# 4093_drone_synth.net
KiCad netlist of a schematic drawn in EAGLE
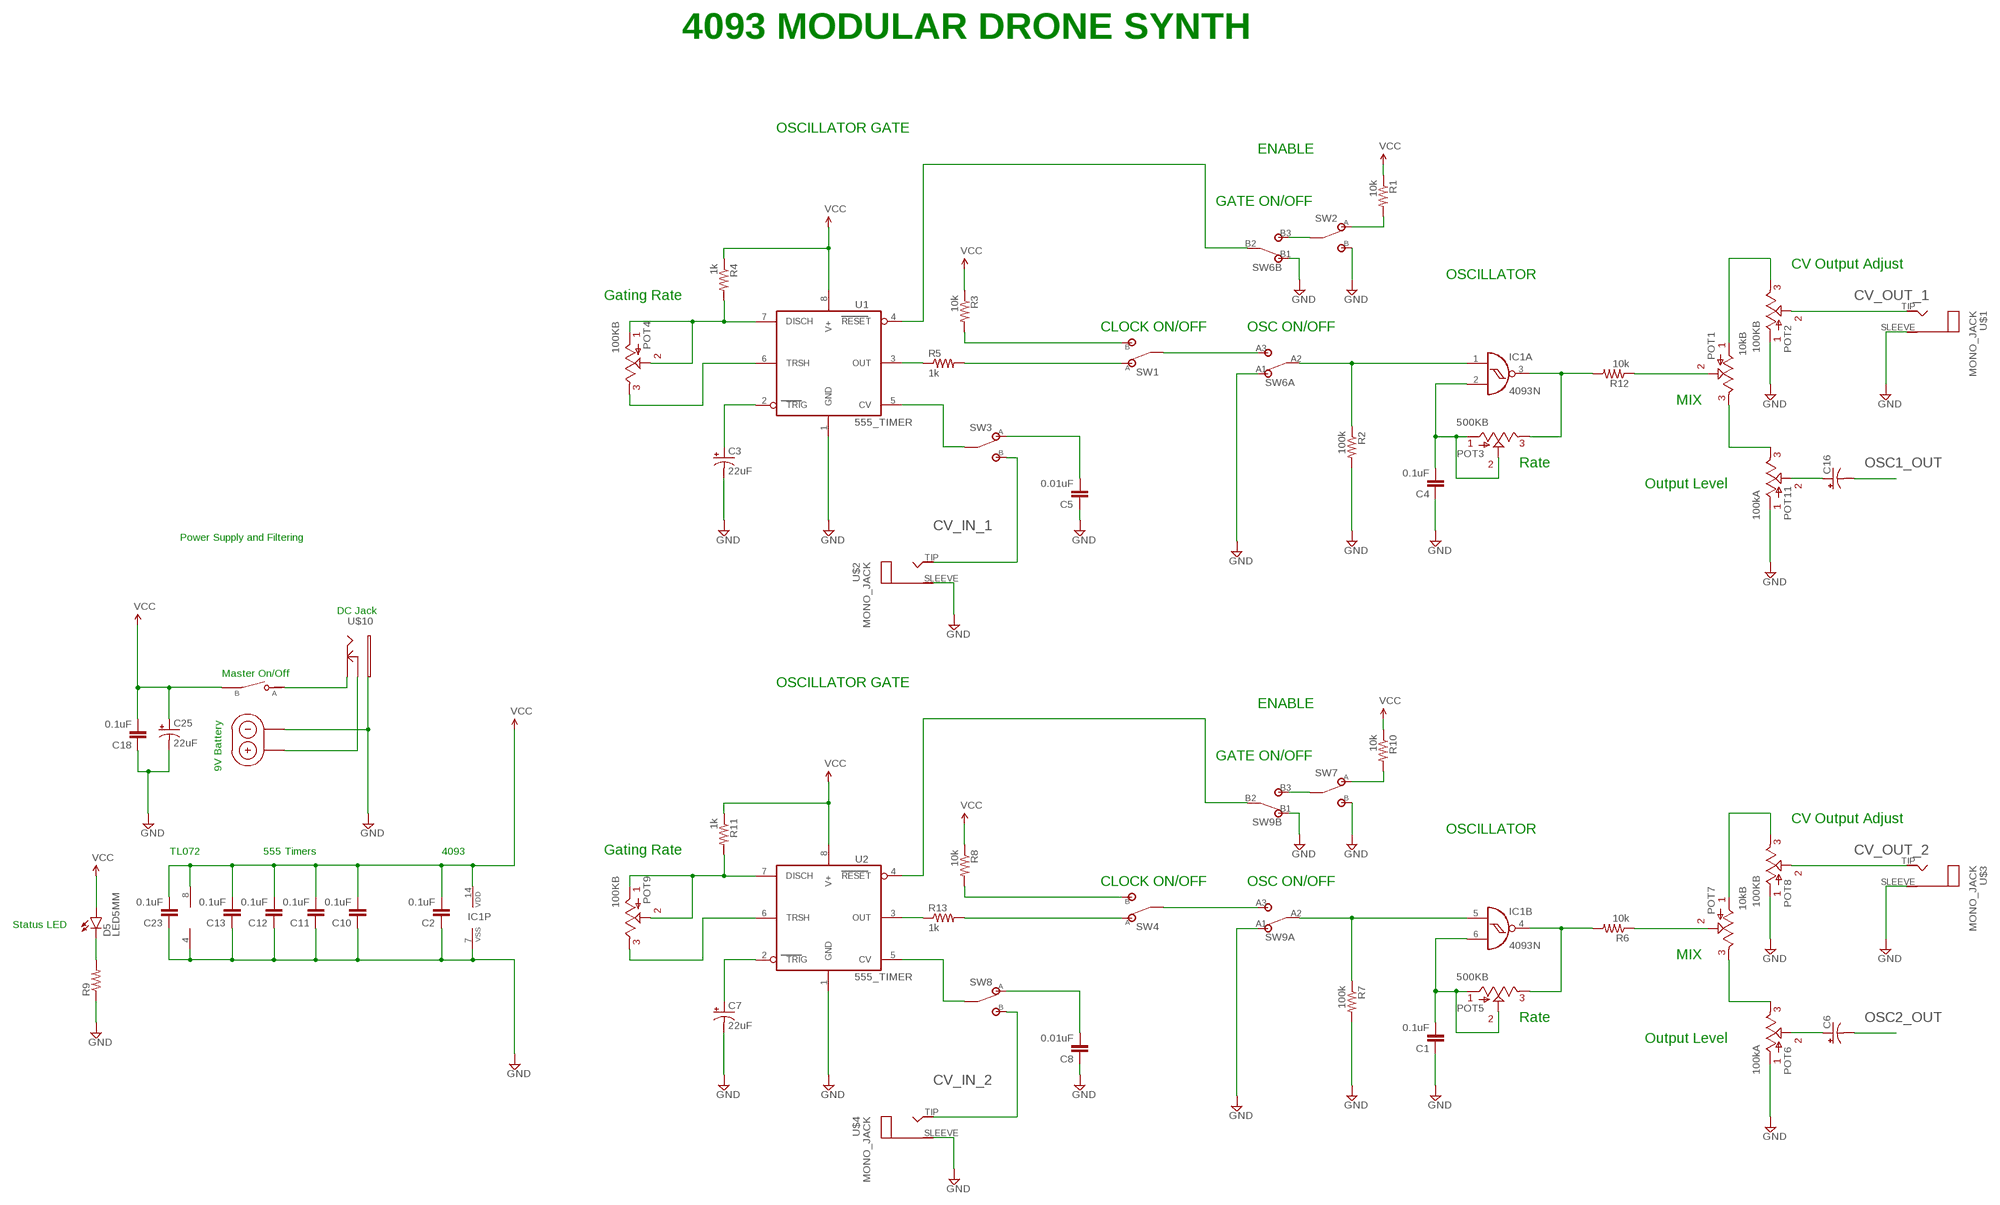
[diagram p0: schematic, sheet 1, part 1 of 3]
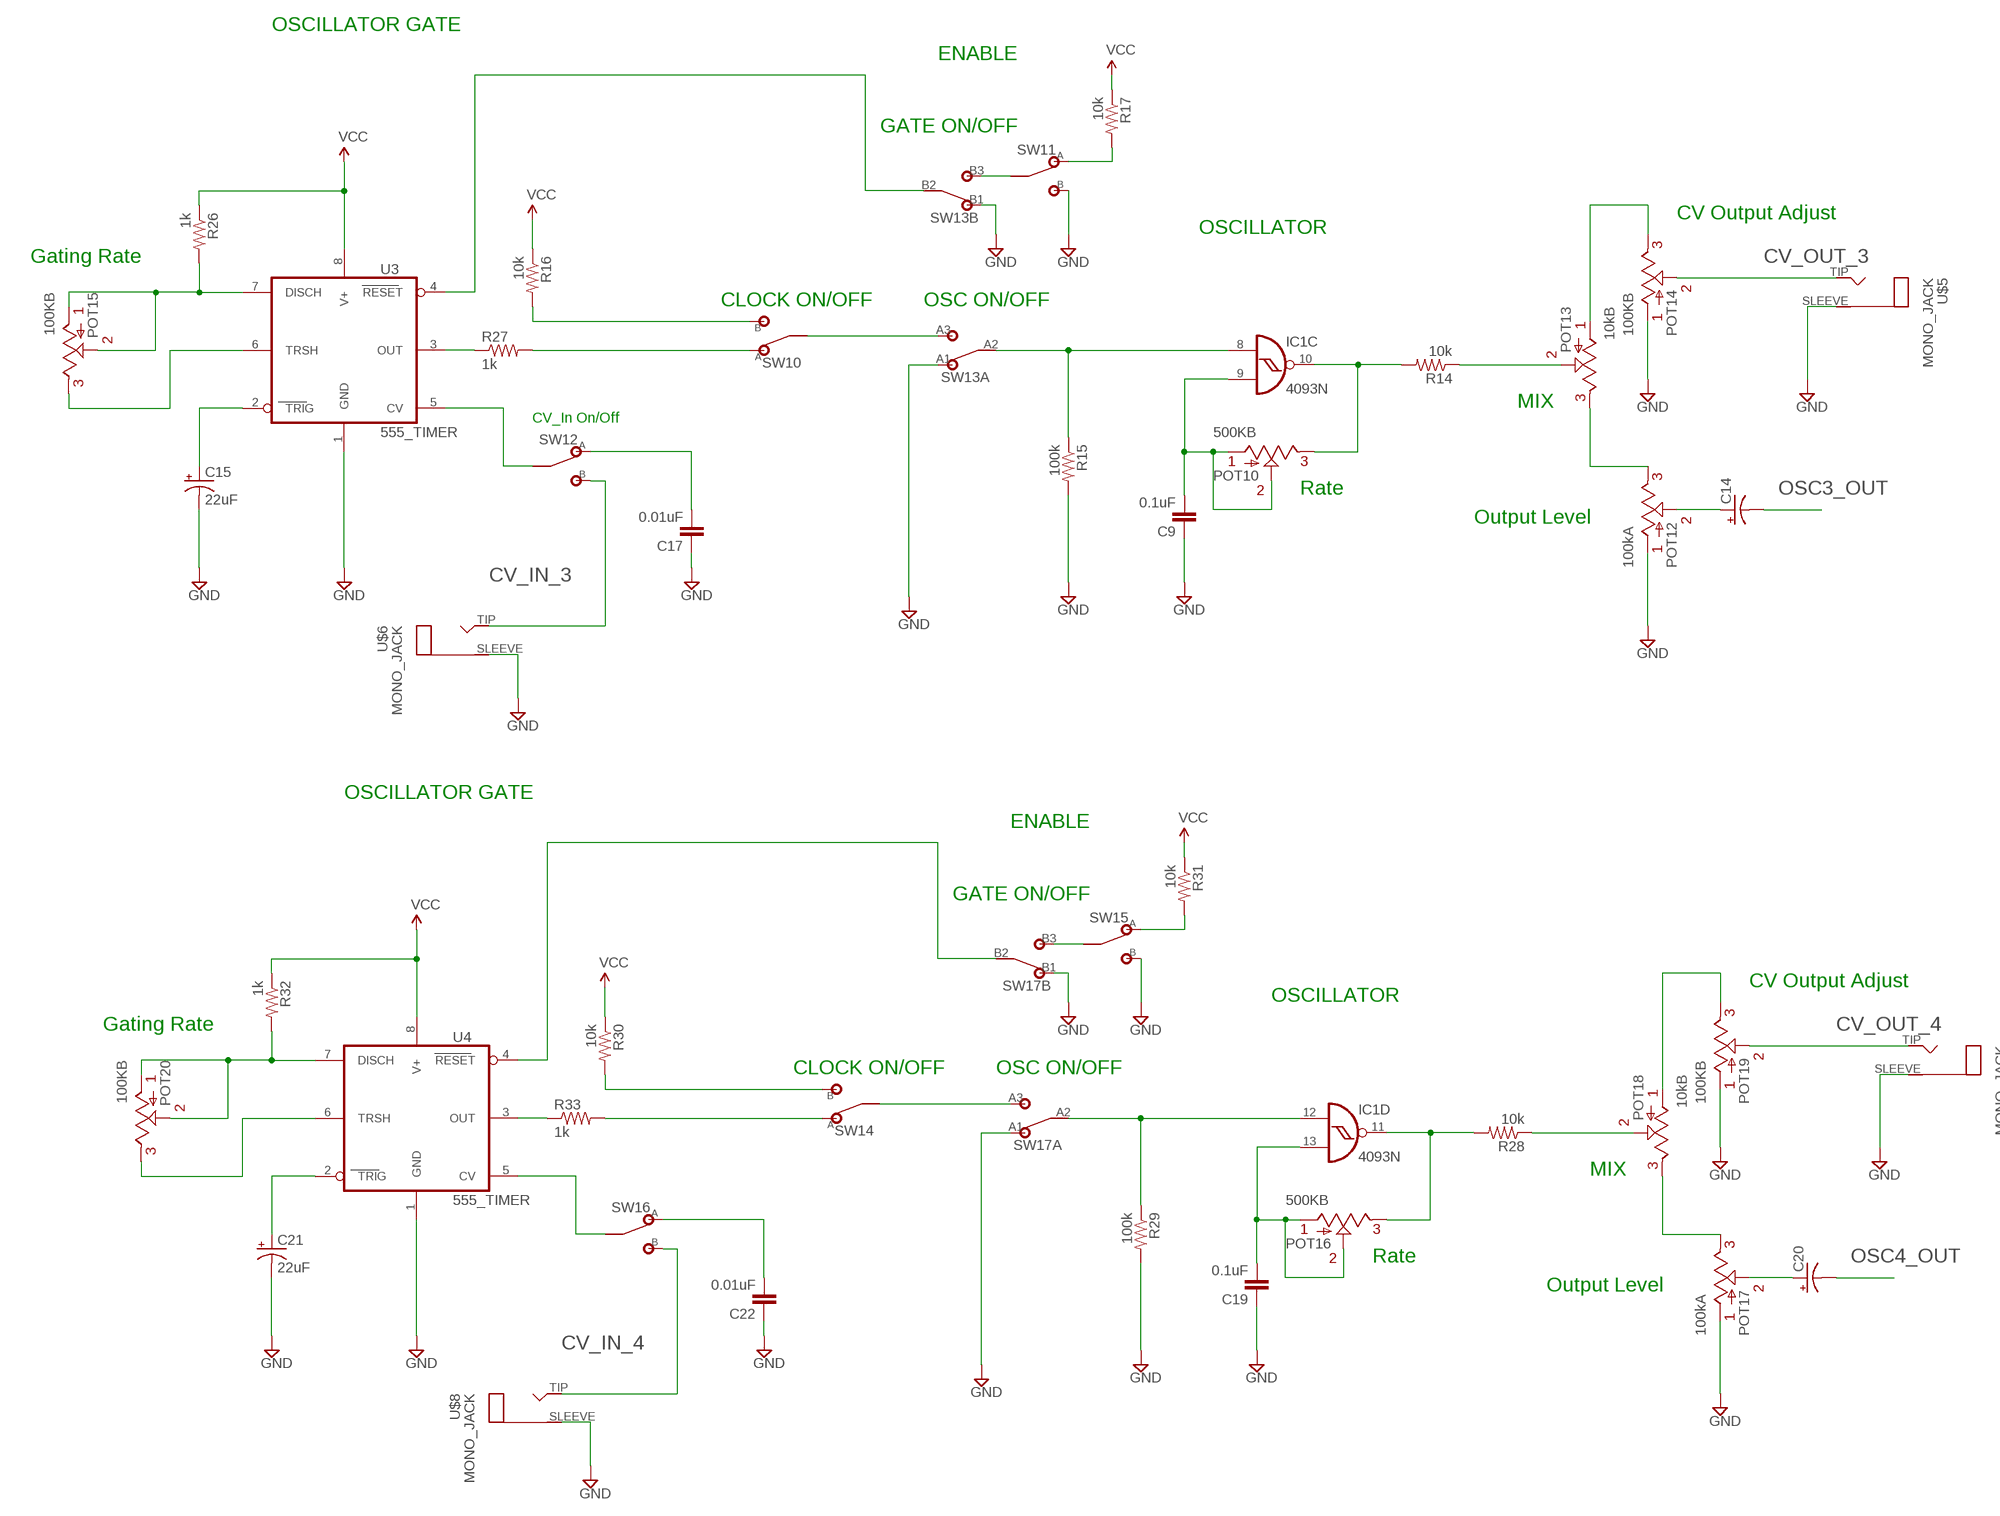
[diagram p1: schematic, sheet 1, part 2 of 3]
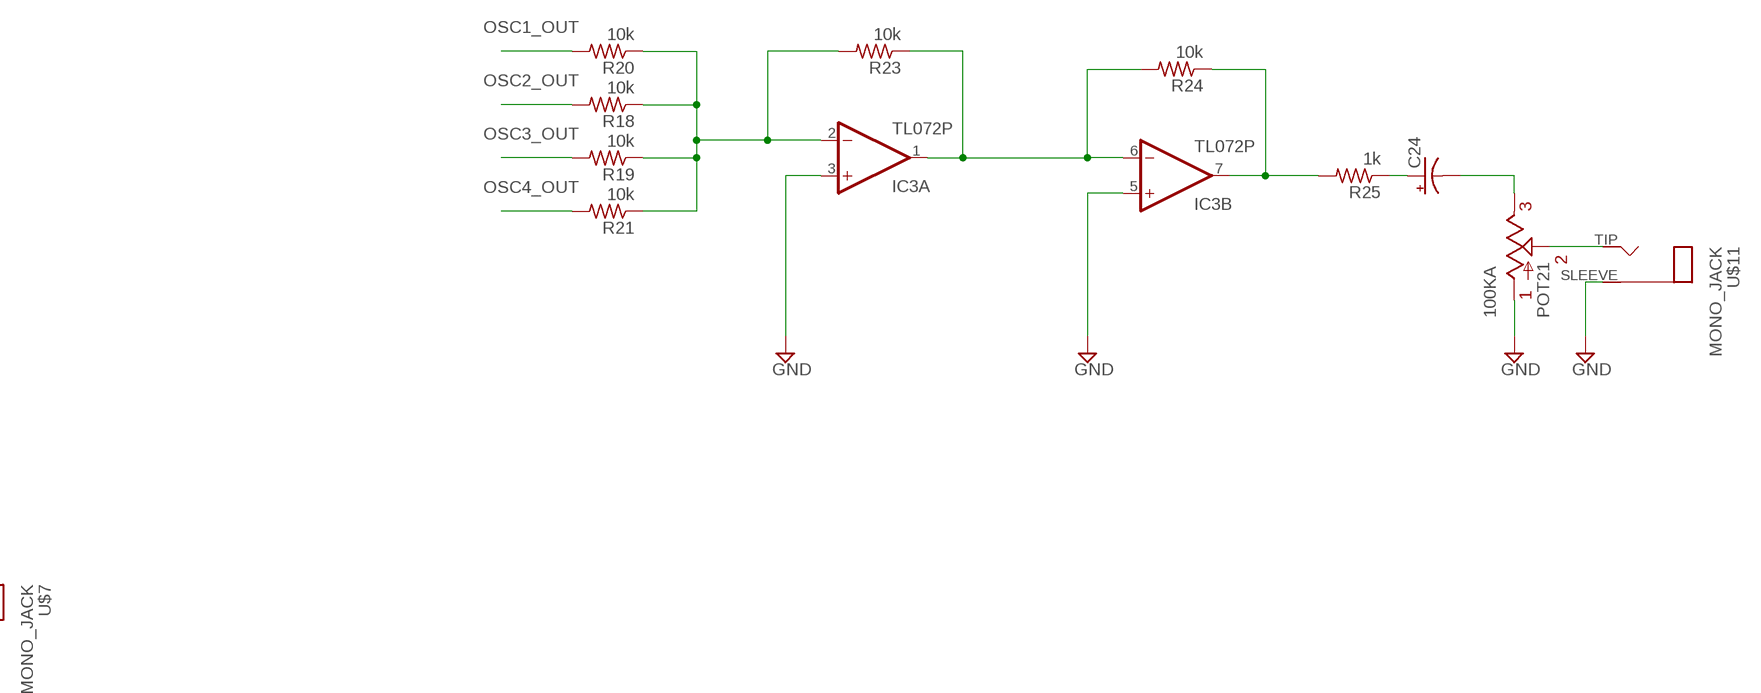
[diagram p2: schematic, sheet 1, part 3 of 3]

(export (version "E")
  (design (tool "Eeschema 10.0.6"))
  (components
    (comp (ref "C1")
      (value "0.1uF")
      (footprint "eagle-import:CERAMIC_CAP")
      (libsource (lib "eagle-import") (part "CERAMIC_CAPACITOR"))
    )
    (comp (ref "C2")
      (value "0.1uF")
      (footprint "eagle-import:CERAMIC_CAP")
      (libsource (lib "eagle-import") (part "CERAMIC_CAPACITOR"))
    )
    (comp (ref "C3")
      (value "22uF")
      (footprint "eagle-import:E5-10,5")
      (libsource (lib "eagle-import") (part "CPOL-USE5-10.5"))
    )
    (comp (ref "C4")
      (value "0.1uF")
      (footprint "eagle-import:CERAMIC_CAP")
      (libsource (lib "eagle-import") (part "CERAMIC_CAPACITOR"))
    )
    (comp (ref "C5")
      (value "0.01uF")
      (footprint "eagle-import:CERAMIC_CAP")
      (libsource (lib "eagle-import") (part "CERAMIC_CAPACITOR"))
    )
    (comp (ref "C6")
      (value "CPOL-USE5-10.5")
      (footprint "eagle-import:E5-10,5")
      (libsource (lib "eagle-import") (part "CPOL-USE5-10.5"))
    )
    (comp (ref "C7")
      (value "22uF")
      (footprint "eagle-import:E5-10,5")
      (libsource (lib "eagle-import") (part "CPOL-USE5-10.5"))
    )
    (comp (ref "C8")
      (value "0.01uF")
      (footprint "eagle-import:CERAMIC_CAP")
      (libsource (lib "eagle-import") (part "CERAMIC_CAPACITOR"))
    )
    (comp (ref "C9")
      (value "0.1uF")
      (footprint "eagle-import:CERAMIC_CAP")
      (libsource (lib "eagle-import") (part "CERAMIC_CAPACITOR"))
    )
    (comp (ref "C10")
      (value "0.1uF")
      (footprint "eagle-import:CERAMIC_CAP")
      (libsource (lib "eagle-import") (part "CERAMIC_CAPACITOR"))
    )
    (comp (ref "C11")
      (value "0.1uF")
      (footprint "eagle-import:CERAMIC_CAP")
      (libsource (lib "eagle-import") (part "CERAMIC_CAPACITOR"))
    )
    (comp (ref "C12")
      (value "0.1uF")
      (footprint "eagle-import:CERAMIC_CAP")
      (libsource (lib "eagle-import") (part "CERAMIC_CAPACITOR"))
    )
    (comp (ref "C13")
      (value "0.1uF")
      (footprint "eagle-import:CERAMIC_CAP")
      (libsource (lib "eagle-import") (part "CERAMIC_CAPACITOR"))
    )
    (comp (ref "C14")
      (value "CPOL-USE5-10.5")
      (footprint "eagle-import:E5-10,5")
      (libsource (lib "eagle-import") (part "CPOL-USE5-10.5"))
    )
    (comp (ref "C15")
      (value "22uF")
      (footprint "eagle-import:E5-10,5")
      (libsource (lib "eagle-import") (part "CPOL-USE5-10.5"))
    )
    (comp (ref "C16")
      (value "CPOL-USE5-10.5")
      (footprint "eagle-import:E5-10,5")
      (libsource (lib "eagle-import") (part "CPOL-USE5-10.5"))
    )
    (comp (ref "C17")
      (value "0.01uF")
      (footprint "eagle-import:CERAMIC_CAP")
      (libsource (lib "eagle-import") (part "CERAMIC_CAPACITOR"))
    )
    (comp (ref "C18")
      (value "0.1uF")
      (footprint "eagle-import:CERAMIC_CAP")
      (libsource (lib "eagle-import") (part "CERAMIC_CAPACITOR"))
    )
    (comp (ref "C19")
      (value "0.1uF")
      (footprint "eagle-import:CERAMIC_CAP")
      (libsource (lib "eagle-import") (part "CERAMIC_CAPACITOR"))
    )
    (comp (ref "C20")
      (value "CPOL-USE5-10.5")
      (footprint "eagle-import:E5-10,5")
      (libsource (lib "eagle-import") (part "CPOL-USE5-10.5"))
    )
    (comp (ref "C21")
      (value "22uF")
      (footprint "eagle-import:E5-10,5")
      (libsource (lib "eagle-import") (part "CPOL-USE5-10.5"))
    )
    (comp (ref "C22")
      (value "0.01uF")
      (footprint "eagle-import:CERAMIC_CAP")
      (libsource (lib "eagle-import") (part "CERAMIC_CAPACITOR"))
    )
    (comp (ref "C23")
      (value "0.1uF")
      (footprint "eagle-import:CERAMIC_CAP")
      (libsource (lib "eagle-import") (part "CERAMIC_CAPACITOR"))
    )
    (comp (ref "C24")
      (value "CPOL-USE5-10.5")
      (footprint "eagle-import:E5-10,5")
      (libsource (lib "eagle-import") (part "CPOL-USE5-10.5"))
    )
    (comp (ref "C25")
      (value "22uF")
      (footprint "eagle-import:E5-10,5")
      (libsource (lib "eagle-import") (part "CPOL-USE5-10.5"))
    )
    (comp (ref "D5")
      (value "LED5MM")
      (footprint "eagle-import:LED5MM")
      (libsource (lib "eagle-import") (part "LED5MM"))
    )
    (comp (ref "IC1")
      (value "4093N")
      (footprint "eagle-import:DIL14")
      (libsource (lib "eagle-import") (part "4093N"))
    )
    (comp (ref "IC3")
      (value "TL072P")
      (footprint "eagle-import:DIL08")
      (libsource (lib "eagle-import") (part "TL072P"))
    )
    (comp (ref "POT1")
      (value "10kB")
      (footprint "eagle-import:POT")
      (libsource (lib "eagle-import") (part "POT"))
    )
    (comp (ref "POT2")
      (value "100KB")
      (footprint "eagle-import:POT")
      (libsource (lib "eagle-import") (part "POT"))
    )
    (comp (ref "POT3")
      (value "500KB")
      (footprint "eagle-import:POT")
      (libsource (lib "eagle-import") (part "POT"))
    )
    (comp (ref "POT4")
      (value "100KB")
      (footprint "eagle-import:POT")
      (libsource (lib "eagle-import") (part "POT"))
    )
    (comp (ref "POT5")
      (value "500KB")
      (footprint "eagle-import:POT")
      (libsource (lib "eagle-import") (part "POT"))
    )
    (comp (ref "POT6")
      (value "100kA")
      (footprint "eagle-import:POT")
      (libsource (lib "eagle-import") (part "POT"))
    )
    (comp (ref "POT7")
      (value "10kB")
      (footprint "eagle-import:POT")
      (libsource (lib "eagle-import") (part "POT"))
    )
    (comp (ref "POT8")
      (value "100KB")
      (footprint "eagle-import:POT")
      (libsource (lib "eagle-import") (part "POT"))
    )
    (comp (ref "POT9")
      (value "100KB")
      (footprint "eagle-import:POT")
      (libsource (lib "eagle-import") (part "POT"))
    )
    (comp (ref "POT10")
      (value "500KB")
      (footprint "eagle-import:POT")
      (libsource (lib "eagle-import") (part "POT"))
    )
    (comp (ref "POT11")
      (value "100kA")
      (footprint "eagle-import:POT")
      (libsource (lib "eagle-import") (part "POT"))
    )
    (comp (ref "POT12")
      (value "100kA")
      (footprint "eagle-import:POT")
      (libsource (lib "eagle-import") (part "POT"))
    )
    (comp (ref "POT13")
      (value "10kB")
      (footprint "eagle-import:POT")
      (libsource (lib "eagle-import") (part "POT"))
    )
    (comp (ref "POT14")
      (value "100KB")
      (footprint "eagle-import:POT")
      (libsource (lib "eagle-import") (part "POT"))
    )
    (comp (ref "POT15")
      (value "100KB")
      (footprint "eagle-import:POT")
      (libsource (lib "eagle-import") (part "POT"))
    )
    (comp (ref "POT16")
      (value "500KB")
      (footprint "eagle-import:POT")
      (libsource (lib "eagle-import") (part "POT"))
    )
    (comp (ref "POT17")
      (value "100kA")
      (footprint "eagle-import:POT")
      (libsource (lib "eagle-import") (part "POT"))
    )
    (comp (ref "POT18")
      (value "10kB")
      (footprint "eagle-import:POT")
      (libsource (lib "eagle-import") (part "POT"))
    )
    (comp (ref "POT19")
      (value "100KB")
      (footprint "eagle-import:POT")
      (libsource (lib "eagle-import") (part "POT"))
    )
    (comp (ref "POT20")
      (value "100KB")
      (footprint "eagle-import:POT")
      (libsource (lib "eagle-import") (part "POT"))
    )
    (comp (ref "POT21")
      (value "100KA")
      (footprint "eagle-import:POT")
      (libsource (lib "eagle-import") (part "POT"))
    )
    (comp (ref "R1")
      (value "10k")
      (footprint "eagle-import:RESISTOR")
      (libsource (lib "eagle-import") (part "RESISTOR"))
    )
    (comp (ref "R2")
      (value "100k")
      (footprint "eagle-import:RESISTOR")
      (libsource (lib "eagle-import") (part "RESISTOR"))
    )
    (comp (ref "R3")
      (value "10k")
      (footprint "eagle-import:RESISTOR")
      (libsource (lib "eagle-import") (part "RESISTOR"))
    )
    (comp (ref "R4")
      (value "1k")
      (footprint "eagle-import:RESISTOR")
      (libsource (lib "eagle-import") (part "RESISTOR"))
    )
    (comp (ref "R5")
      (value "1k")
      (footprint "eagle-import:RESISTOR")
      (libsource (lib "eagle-import") (part "RESISTOR"))
    )
    (comp (ref "R6")
      (value "10k")
      (footprint "eagle-import:RESISTOR")
      (libsource (lib "eagle-import") (part "RESISTOR"))
    )
    (comp (ref "R7")
      (value "100k")
      (footprint "eagle-import:RESISTOR")
      (libsource (lib "eagle-import") (part "RESISTOR"))
    )
    (comp (ref "R8")
      (value "10k")
      (footprint "eagle-import:RESISTOR")
      (libsource (lib "eagle-import") (part "RESISTOR"))
    )
    (comp (ref "R9")
      (value "RESISTOR")
      (footprint "eagle-import:RESISTOR")
      (libsource (lib "eagle-import") (part "RESISTOR"))
    )
    (comp (ref "R10")
      (value "10k")
      (footprint "eagle-import:RESISTOR")
      (libsource (lib "eagle-import") (part "RESISTOR"))
    )
    (comp (ref "R11")
      (value "1k")
      (footprint "eagle-import:RESISTOR")
      (libsource (lib "eagle-import") (part "RESISTOR"))
    )
    (comp (ref "R12")
      (value "10k")
      (footprint "eagle-import:RESISTOR")
      (libsource (lib "eagle-import") (part "RESISTOR"))
    )
    (comp (ref "R13")
      (value "1k")
      (footprint "eagle-import:RESISTOR")
      (libsource (lib "eagle-import") (part "RESISTOR"))
    )
    (comp (ref "R14")
      (value "10k")
      (footprint "eagle-import:RESISTOR")
      (libsource (lib "eagle-import") (part "RESISTOR"))
    )
    (comp (ref "R15")
      (value "100k")
      (footprint "eagle-import:RESISTOR")
      (libsource (lib "eagle-import") (part "RESISTOR"))
    )
    (comp (ref "R16")
      (value "10k")
      (footprint "eagle-import:RESISTOR")
      (libsource (lib "eagle-import") (part "RESISTOR"))
    )
    (comp (ref "R17")
      (value "10k")
      (footprint "eagle-import:RESISTOR")
      (libsource (lib "eagle-import") (part "RESISTOR"))
    )
    (comp (ref "R18")
      (value "10k")
      (footprint "eagle-import:RESISTOR")
      (libsource (lib "eagle-import") (part "RESISTOR"))
    )
    (comp (ref "R19")
      (value "10k")
      (footprint "eagle-import:RESISTOR")
      (libsource (lib "eagle-import") (part "RESISTOR"))
    )
    (comp (ref "R20")
      (value "10k")
      (footprint "eagle-import:RESISTOR")
      (libsource (lib "eagle-import") (part "RESISTOR"))
    )
    (comp (ref "R21")
      (value "10k")
      (footprint "eagle-import:RESISTOR")
      (libsource (lib "eagle-import") (part "RESISTOR"))
    )
    (comp (ref "R23")
      (value "10k")
      (footprint "eagle-import:RESISTOR")
      (libsource (lib "eagle-import") (part "RESISTOR"))
    )
    (comp (ref "R24")
      (value "10k")
      (footprint "eagle-import:RESISTOR")
      (libsource (lib "eagle-import") (part "RESISTOR"))
    )
    (comp (ref "R25")
      (value "1k")
      (footprint "eagle-import:RESISTOR")
      (libsource (lib "eagle-import") (part "RESISTOR"))
    )
    (comp (ref "R26")
      (value "1k")
      (footprint "eagle-import:RESISTOR")
      (libsource (lib "eagle-import") (part "RESISTOR"))
    )
    (comp (ref "R27")
      (value "1k")
      (footprint "eagle-import:RESISTOR")
      (libsource (lib "eagle-import") (part "RESISTOR"))
    )
    (comp (ref "R28")
      (value "10k")
      (footprint "eagle-import:RESISTOR")
      (libsource (lib "eagle-import") (part "RESISTOR"))
    )
    (comp (ref "R29")
      (value "100k")
      (footprint "eagle-import:RESISTOR")
      (libsource (lib "eagle-import") (part "RESISTOR"))
    )
    (comp (ref "R30")
      (value "10k")
      (footprint "eagle-import:RESISTOR")
      (libsource (lib "eagle-import") (part "RESISTOR"))
    )
    (comp (ref "R31")
      (value "10k")
      (footprint "eagle-import:RESISTOR")
      (libsource (lib "eagle-import") (part "RESISTOR"))
    )
    (comp (ref "R32")
      (value "1k")
      (footprint "eagle-import:RESISTOR")
      (libsource (lib "eagle-import") (part "RESISTOR"))
    )
    (comp (ref "R33")
      (value "1k")
      (footprint "eagle-import:RESISTOR")
      (libsource (lib "eagle-import") (part "RESISTOR"))
    )
    (comp (ref "SW1")
      (value "SPDT_SWITCH")
      (footprint "eagle-import:SPDT_TOGGLE_SWITCH")
      (libsource (lib "eagle-import") (part "SPDT_SWITCH"))
    )
    (comp (ref "SW2")
      (value "SPDT_SWITCH")
      (footprint "eagle-import:SPDT_TOGGLE_SWITCH")
      (libsource (lib "eagle-import") (part "SPDT_SWITCH"))
    )
    (comp (ref "SW3")
      (value "SPDT_SWITCH")
      (footprint "eagle-import:SPDT_TOGGLE_SWITCH")
      (libsource (lib "eagle-import") (part "SPDT_SWITCH"))
    )
    (comp (ref "SW4")
      (value "SPDT_SWITCH")
      (footprint "eagle-import:SPDT_TOGGLE_SWITCH")
      (libsource (lib "eagle-import") (part "SPDT_SWITCH"))
    )
    (comp (ref "SW6")
      (value "DPDT")
      (footprint "eagle-import:DPDT")
      (libsource (lib "eagle-import") (part "DPDT"))
    )
    (comp (ref "SW7")
      (value "SPDT_SWITCH")
      (footprint "eagle-import:SPDT_TOGGLE_SWITCH")
      (libsource (lib "eagle-import") (part "SPDT_SWITCH"))
    )
    (comp (ref "SW8")
      (value "SPDT_SWITCH")
      (footprint "eagle-import:SPDT_TOGGLE_SWITCH")
      (libsource (lib "eagle-import") (part "SPDT_SWITCH"))
    )
    (comp (ref "SW9")
      (value "DPDT")
      (footprint "eagle-import:DPDT")
      (libsource (lib "eagle-import") (part "DPDT"))
    )
    (comp (ref "SW10")
      (value "SPDT_SWITCH")
      (footprint "eagle-import:SPDT_TOGGLE_SWITCH")
      (libsource (lib "eagle-import") (part "SPDT_SWITCH"))
    )
    (comp (ref "SW11")
      (value "SPDT_SWITCH")
      (footprint "eagle-import:SPDT_TOGGLE_SWITCH")
      (libsource (lib "eagle-import") (part "SPDT_SWITCH"))
    )
    (comp (ref "SW12")
      (value "SPDT_SWITCH")
      (footprint "eagle-import:SPDT_TOGGLE_SWITCH")
      (libsource (lib "eagle-import") (part "SPDT_SWITCH"))
    )
    (comp (ref "SW13")
      (value "DPDT")
      (footprint "eagle-import:DPDT")
      (libsource (lib "eagle-import") (part "DPDT"))
    )
    (comp (ref "SW14")
      (value "SPDT_SWITCH")
      (footprint "eagle-import:SPDT_TOGGLE_SWITCH")
      (libsource (lib "eagle-import") (part "SPDT_SWITCH"))
    )
    (comp (ref "SW15")
      (value "SPDT_SWITCH")
      (footprint "eagle-import:SPDT_TOGGLE_SWITCH")
      (libsource (lib "eagle-import") (part "SPDT_SWITCH"))
    )
    (comp (ref "SW16")
      (value "SPDT_SWITCH")
      (footprint "eagle-import:SPDT_TOGGLE_SWITCH")
      (libsource (lib "eagle-import") (part "SPDT_SWITCH"))
    )
    (comp (ref "SW17")
      (value "DPDT")
      (footprint "eagle-import:DPDT")
      (libsource (lib "eagle-import") (part "DPDT"))
    )
    (comp (ref "SW18")
      (value "SPST_SWITCH")
      (footprint "eagle-import:SPST_TOGGLE_SWITCH")
      (libsource (lib "eagle-import") (part "SPST_SWITCH"))
    )
    (comp (ref "U$1")
      (value "MONO_JACK")
      (footprint "eagle-import:MONO_JACK")
      (libsource (lib "eagle-import") (part "MONO_JACK"))
    )
    (comp (ref "U$2")
      (value "MONO_JACK")
      (footprint "eagle-import:MONO_JACK")
      (libsource (lib "eagle-import") (part "MONO_JACK"))
    )
    (comp (ref "U$3")
      (value "MONO_JACK")
      (footprint "eagle-import:MONO_JACK")
      (libsource (lib "eagle-import") (part "MONO_JACK"))
    )
    (comp (ref "U$4")
      (value "MONO_JACK")
      (footprint "eagle-import:MONO_JACK")
      (libsource (lib "eagle-import") (part "MONO_JACK"))
    )
    (comp (ref "U$5")
      (value "MONO_JACK")
      (footprint "eagle-import:MONO_JACK")
      (libsource (lib "eagle-import") (part "MONO_JACK"))
    )
    (comp (ref "U$6")
      (value "MONO_JACK")
      (footprint "eagle-import:MONO_JACK")
      (libsource (lib "eagle-import") (part "MONO_JACK"))
    )
    (comp (ref "U$7")
      (value "MONO_JACK")
      (footprint "eagle-import:MONO_JACK")
      (libsource (lib "eagle-import") (part "MONO_JACK"))
    )
    (comp (ref "U$8")
      (value "MONO_JACK")
      (footprint "eagle-import:MONO_JACK")
      (libsource (lib "eagle-import") (part "MONO_JACK"))
    )
    (comp (ref "U$9")
      (value "9V_BATTERY_CLIP")
      (footprint "eagle-import:9V_BATTERY")
      (libsource (lib "eagle-import") (part "9V_BATTERY_CLIP"))
    )
    (comp (ref "U$10")
      (value "DC_JACK_OFFBOARD")
      (footprint "eagle-import:DC_JACK_OFFBOARD")
      (libsource (lib "eagle-import") (part "DC_JACK_OFFBOARD"))
    )
    (comp (ref "U$11")
      (value "MONO_JACK")
      (footprint "eagle-import:MONO_JACK")
      (libsource (lib "eagle-import") (part "MONO_JACK"))
    )
    (comp (ref "U1")
      (value "555_TIMER")
      (footprint "eagle-import:DIL08")
      (libsource (lib "eagle-import") (part "555_TIMER"))
    )
    (comp (ref "U2")
      (value "555_TIMER")
      (footprint "eagle-import:DIL08")
      (libsource (lib "eagle-import") (part "555_TIMER"))
    )
    (comp (ref "U3")
      (value "555_TIMER")
      (footprint "eagle-import:DIL08")
      (libsource (lib "eagle-import") (part "555_TIMER"))
    )
    (comp (ref "U4")
      (value "555_TIMER")
      (footprint "eagle-import:DIL08")
      (libsource (lib "eagle-import") (part "555_TIMER"))
    )
  )
  (nets
    (net (code "1") (name "/CV_IN_1") (class "Default")
      (node (ref "SW3") (pin "B") (pinfunction "B_B") (pintype "passive"))
      (node (ref "U$2") (pin "TIP") (pinfunction "TIP_TIP") (pintype "passive"))
    )
    (net (code "2") (name "/CV_IN_2") (class "Default")
      (node (ref "SW8") (pin "B") (pinfunction "B_B") (pintype "passive"))
      (node (ref "U$4") (pin "TIP") (pinfunction "TIP_TIP") (pintype "passive"))
    )
    (net (code "3") (name "/CV_IN_3") (class "Default")
      (node (ref "SW12") (pin "B") (pinfunction "B_B") (pintype "passive"))
      (node (ref "U$6") (pin "TIP") (pinfunction "TIP_TIP") (pintype "passive"))
    )
    (net (code "4") (name "/CV_IN_4") (class "Default")
      (node (ref "SW16") (pin "B") (pinfunction "B_B") (pintype "passive"))
      (node (ref "U$8") (pin "TIP") (pinfunction "TIP_TIP") (pintype "passive"))
    )
    (net (code "5") (name "/CV_OUT_1") (class "Default")
      (node (ref "POT2") (pin "2") (pinfunction "2_2") (pintype "passive"))
      (node (ref "U$1") (pin "TIP") (pinfunction "TIP_TIP") (pintype "passive"))
    )
    (net (code "6") (name "/CV_OUT_2") (class "Default")
      (node (ref "POT8") (pin "2") (pinfunction "2_2") (pintype "passive"))
      (node (ref "U$3") (pin "TIP") (pinfunction "TIP_TIP") (pintype "passive"))
    )
    (net (code "7") (name "/CV_OUT_3") (class "Default")
      (node (ref "POT14") (pin "2") (pinfunction "2_2") (pintype "passive"))
      (node (ref "U$5") (pin "TIP") (pinfunction "TIP_TIP") (pintype "passive"))
    )
    (net (code "8") (name "/CV_OUT_4") (class "Default")
      (node (ref "POT19") (pin "2") (pinfunction "2_2") (pintype "passive"))
      (node (ref "U$7") (pin "TIP") (pinfunction "TIP_TIP") (pintype "passive"))
    )
    (net (code "9") (name "/OSC1_OUT") (class "Default")
      (node (ref "C16") (pin "-") (pinfunction "-_-") (pintype "passive"))
      (node (ref "R20") (pin "2") (pinfunction "2_2") (pintype "passive"))
    )
    (net (code "10") (name "/OSC2_OUT") (class "Default")
      (node (ref "C6") (pin "-") (pinfunction "-_-") (pintype "passive"))
      (node (ref "R18") (pin "2") (pinfunction "2_2") (pintype "passive"))
    )
    (net (code "11") (name "/OSC3_OUT") (class "Default")
      (node (ref "C14") (pin "-") (pinfunction "-_-") (pintype "passive"))
      (node (ref "R19") (pin "2") (pinfunction "2_2") (pintype "passive"))
    )
    (net (code "12") (name "/OSC4_OUT") (class "Default")
      (node (ref "C20") (pin "-") (pinfunction "-_-") (pintype "passive"))
      (node (ref "R21") (pin "2") (pinfunction "2_2") (pintype "passive"))
    )
    (net (code "13") (name "GND") (class "Default")
      (node (ref "C1") (pin "1") (pinfunction "1_1") (pintype "passive"))
      (node (ref "C10") (pin "1") (pinfunction "1_1") (pintype "passive"))
      (node (ref "C11") (pin "1") (pinfunction "1_1") (pintype "passive"))
      (node (ref "C12") (pin "1") (pinfunction "1_1") (pintype "passive"))
      (node (ref "C13") (pin "1") (pinfunction "1_1") (pintype "passive"))
      (node (ref "C15") (pin "-") (pinfunction "-_-") (pintype "passive"))
      (node (ref "C17") (pin "1") (pinfunction "1_1") (pintype "passive"))
      (node (ref "C18") (pin "1") (pinfunction "1_1") (pintype "passive"))
      (node (ref "C19") (pin "1") (pinfunction "1_1") (pintype "passive"))
      (node (ref "C2") (pin "1") (pinfunction "1_1") (pintype "passive"))
      (node (ref "C21") (pin "-") (pinfunction "-_-") (pintype "passive"))
      (node (ref "C22") (pin "1") (pinfunction "1_1") (pintype "passive"))
      (node (ref "C23") (pin "1") (pinfunction "1_1") (pintype "passive"))
      (node (ref "C25") (pin "-") (pinfunction "-_-") (pintype "passive"))
      (node (ref "C3") (pin "-") (pinfunction "-_-") (pintype "passive"))
      (node (ref "C4") (pin "1") (pinfunction "1_1") (pintype "passive"))
      (node (ref "C5") (pin "1") (pinfunction "1_1") (pintype "passive"))
      (node (ref "C7") (pin "-") (pinfunction "-_-") (pintype "passive"))
      (node (ref "C8") (pin "1") (pinfunction "1_1") (pintype "passive"))
      (node (ref "C9") (pin "1") (pinfunction "1_1") (pintype "passive"))
      (node (ref "IC1") (pin "7") (pinfunction "VSS_7") (pintype "power_in"))
      (node (ref "IC3") (pin "3") (pinfunction "+IN_3") (pintype "input"))
      (node (ref "IC3") (pin "4") (pinfunction "V-_4") (pintype "power_in"))
      (node (ref "IC3") (pin "5") (pinfunction "+IN_5") (pintype "input"))
      (node (ref "POT11") (pin "1") (pinfunction "1_1") (pintype "passive"))
      (node (ref "POT12") (pin "1") (pinfunction "1_1") (pintype "passive"))
      (node (ref "POT14") (pin "1") (pinfunction "1_1") (pintype "passive"))
      (node (ref "POT17") (pin "1") (pinfunction "1_1") (pintype "passive"))
      (node (ref "POT19") (pin "1") (pinfunction "1_1") (pintype "passive"))
      (node (ref "POT2") (pin "1") (pinfunction "1_1") (pintype "passive"))
      (node (ref "POT21") (pin "1") (pinfunction "1_1") (pintype "passive"))
      (node (ref "POT6") (pin "1") (pinfunction "1_1") (pintype "passive"))
      (node (ref "POT8") (pin "1") (pinfunction "1_1") (pintype "passive"))
      (node (ref "R15") (pin "2") (pinfunction "2_2") (pintype "passive"))
      (node (ref "R2") (pin "2") (pinfunction "2_2") (pintype "passive"))
      (node (ref "R29") (pin "2") (pinfunction "2_2") (pintype "passive"))
      (node (ref "R7") (pin "2") (pinfunction "2_2") (pintype "passive"))
      (node (ref "R9") (pin "1") (pinfunction "1_1") (pintype "passive"))
      (node (ref "SW11") (pin "B") (pinfunction "B_B") (pintype "passive"))
      (node (ref "SW13") (pin "A1") (pinfunction "1_A1") (pintype "passive"))
      (node (ref "SW13") (pin "B1") (pinfunction "1_B1") (pintype "passive"))
      (node (ref "SW15") (pin "B") (pinfunction "B_B") (pintype "passive"))
      (node (ref "SW17") (pin "A1") (pinfunction "1_A1") (pintype "passive"))
      (node (ref "SW17") (pin "B1") (pinfunction "1_B1") (pintype "passive"))
      (node (ref "SW2") (pin "B") (pinfunction "B_B") (pintype "passive"))
      (node (ref "SW6") (pin "A1") (pinfunction "1_A1") (pintype "passive"))
      (node (ref "SW6") (pin "B1") (pinfunction "1_B1") (pintype "passive"))
      (node (ref "SW7") (pin "B") (pinfunction "B_B") (pintype "passive"))
      (node (ref "SW9") (pin "A1") (pinfunction "1_A1") (pintype "passive"))
      (node (ref "SW9") (pin "B1") (pinfunction "1_B1") (pintype "passive"))
      (node (ref "U$1") (pin "SLEEVE") (pinfunction "SLEEVE_SLEEVE") (pintype "passive"))
      (node (ref "U$10") (pin "PIN") (pinfunction "PIN_PIN") (pintype "bidirectional"))
      (node (ref "U$11") (pin "SLEEVE") (pinfunction "SLEEVE_SLEEVE") (pintype "passive"))
      (node (ref "U$2") (pin "SLEEVE") (pinfunction "SLEEVE_SLEEVE") (pintype "passive"))
      (node (ref "U$3") (pin "SLEEVE") (pinfunction "SLEEVE_SLEEVE") (pintype "passive"))
      (node (ref "U$4") (pin "SLEEVE") (pinfunction "SLEEVE_SLEEVE") (pintype "passive"))
      (node (ref "U$5") (pin "SLEEVE") (pinfunction "SLEEVE_SLEEVE") (pintype "passive"))
      (node (ref "U$6") (pin "SLEEVE") (pinfunction "SLEEVE_SLEEVE") (pintype "passive"))
      (node (ref "U$7") (pin "SLEEVE") (pinfunction "SLEEVE_SLEEVE") (pintype "passive"))
      (node (ref "U$8") (pin "SLEEVE") (pinfunction "SLEEVE_SLEEVE") (pintype "passive"))
      (node (ref "U$9") (pin "9V_BATTERY_-") (pinfunction "9V_BATTERY_-_9V_BATTERY_-") (pintype "power_in"))
      (node (ref "U1") (pin "1") (pinfunction "GND_1") (pintype "power_in"))
      (node (ref "U2") (pin "1") (pinfunction "GND_1") (pintype "power_in"))
      (node (ref "U3") (pin "1") (pinfunction "GND_1") (pintype "power_in"))
      (node (ref "U4") (pin "1") (pinfunction "GND_1") (pintype "power_in"))
    )
    (net (code "14") (name "Net-(C5-Pad2)") (class "Default")
      (node (ref "C5") (pin "2") (pinfunction "2_2") (pintype "passive"))
      (node (ref "SW3") (pin "A") (pinfunction "A_A") (pintype "passive"))
    )
    (net (code "15") (name "Net-(C6-Pad+)") (class "Default")
      (node (ref "C6") (pin "+") (pinfunction "+_+") (pintype "passive"))
      (node (ref "POT6") (pin "2") (pinfunction "2_2") (pintype "passive"))
    )
    (net (code "16") (name "Net-(C8-Pad2)") (class "Default")
      (node (ref "C8") (pin "2") (pinfunction "2_2") (pintype "passive"))
      (node (ref "SW8") (pin "A") (pinfunction "A_A") (pintype "passive"))
    )
    (net (code "17") (name "Net-(C14-Pad+)") (class "Default")
      (node (ref "C14") (pin "+") (pinfunction "+_+") (pintype "passive"))
      (node (ref "POT12") (pin "2") (pinfunction "2_2") (pintype "passive"))
    )
    (net (code "18") (name "Net-(C16-Pad+)") (class "Default")
      (node (ref "C16") (pin "+") (pinfunction "+_+") (pintype "passive"))
      (node (ref "POT11") (pin "2") (pinfunction "2_2") (pintype "passive"))
    )
    (net (code "19") (name "Net-(C17-Pad2)") (class "Default")
      (node (ref "C17") (pin "2") (pinfunction "2_2") (pintype "passive"))
      (node (ref "SW12") (pin "A") (pinfunction "A_A") (pintype "passive"))
    )
    (net (code "20") (name "Net-(C20-Pad+)") (class "Default")
      (node (ref "C20") (pin "+") (pinfunction "+_+") (pintype "passive"))
      (node (ref "POT17") (pin "2") (pinfunction "2_2") (pintype "passive"))
    )
    (net (code "21") (name "Net-(C22-Pad2)") (class "Default")
      (node (ref "C22") (pin "2") (pinfunction "2_2") (pintype "passive"))
      (node (ref "SW16") (pin "A") (pinfunction "A_A") (pintype "passive"))
    )
    (net (code "22") (name "Net-(C24-Pad+)") (class "Default")
      (node (ref "C24") (pin "+") (pinfunction "+_+") (pintype "passive"))
      (node (ref "R25") (pin "1") (pinfunction "1_1") (pintype "passive"))
    )
    (net (code "23") (name "Net-(C24-Pad-)") (class "Default")
      (node (ref "C24") (pin "-") (pinfunction "-_-") (pintype "passive"))
      (node (ref "POT21") (pin "3") (pinfunction "3_3") (pintype "passive"))
    )
    (net (code "24") (name "Net-(D5-C)") (class "Default")
      (node (ref "D5") (pin "K") (pinfunction "C_K") (pintype "passive"))
      (node (ref "R9") (pin "2") (pinfunction "2_2") (pintype "passive"))
    )
    (net (code "25") (name "Net-(IC1A-I0)") (class "Default")
      (node (ref "IC1") (pin "1") (pinfunction "I0_1") (pintype "input"))
      (node (ref "R2") (pin "1") (pinfunction "1_1") (pintype "passive"))
      (node (ref "SW6") (pin "A2") (pinfunction "2_A2") (pintype "passive"))
    )
    (net (code "26") (name "Net-(IC1A-I1)") (class "Default")
      (node (ref "C4") (pin "2") (pinfunction "2_2") (pintype "passive"))
      (node (ref "IC1") (pin "2") (pinfunction "I1_2") (pintype "input"))
      (node (ref "POT3") (pin "1") (pinfunction "1_1") (pintype "passive"))
      (node (ref "POT3") (pin "2") (pinfunction "2_2") (pintype "passive"))
    )
    (net (code "27") (name "Net-(IC1A-O)") (class "Default")
      (node (ref "IC1") (pin "3") (pinfunction "O_3") (pintype "output"))
      (node (ref "POT3") (pin "3") (pinfunction "3_3") (pintype "passive"))
      (node (ref "R12") (pin "2") (pinfunction "2_2") (pintype "passive"))
    )
    (net (code "28") (name "Net-(IC1B-I0)") (class "Default")
      (node (ref "IC1") (pin "5") (pinfunction "I0_5") (pintype "input"))
      (node (ref "R7") (pin "1") (pinfunction "1_1") (pintype "passive"))
      (node (ref "SW9") (pin "A2") (pinfunction "2_A2") (pintype "passive"))
    )
    (net (code "29") (name "Net-(IC1B-I1)") (class "Default")
      (node (ref "C1") (pin "2") (pinfunction "2_2") (pintype "passive"))
      (node (ref "IC1") (pin "6") (pinfunction "I1_6") (pintype "input"))
      (node (ref "POT5") (pin "1") (pinfunction "1_1") (pintype "passive"))
      (node (ref "POT5") (pin "2") (pinfunction "2_2") (pintype "passive"))
    )
    (net (code "30") (name "Net-(IC1B-O)") (class "Default")
      (node (ref "IC1") (pin "4") (pinfunction "O_4") (pintype "output"))
      (node (ref "POT5") (pin "3") (pinfunction "3_3") (pintype "passive"))
      (node (ref "R6") (pin "2") (pinfunction "2_2") (pintype "passive"))
    )
    (net (code "31") (name "Net-(IC1C-I0)") (class "Default")
      (node (ref "IC1") (pin "8") (pinfunction "I0_8") (pintype "input"))
      (node (ref "R15") (pin "1") (pinfunction "1_1") (pintype "passive"))
      (node (ref "SW13") (pin "A2") (pinfunction "2_A2") (pintype "passive"))
    )
    (net (code "32") (name "Net-(IC1C-I1)") (class "Default")
      (node (ref "C9") (pin "2") (pinfunction "2_2") (pintype "passive"))
      (node (ref "IC1") (pin "9") (pinfunction "I1_9") (pintype "input"))
      (node (ref "POT10") (pin "1") (pinfunction "1_1") (pintype "passive"))
      (node (ref "POT10") (pin "2") (pinfunction "2_2") (pintype "passive"))
    )
    (net (code "33") (name "Net-(IC1C-O)") (class "Default")
      (node (ref "IC1") (pin "10") (pinfunction "O_10") (pintype "output"))
      (node (ref "POT10") (pin "3") (pinfunction "3_3") (pintype "passive"))
      (node (ref "R14") (pin "2") (pinfunction "2_2") (pintype "passive"))
    )
    (net (code "34") (name "Net-(IC1D-I0)") (class "Default")
      (node (ref "IC1") (pin "12") (pinfunction "I0_12") (pintype "input"))
      (node (ref "R29") (pin "1") (pinfunction "1_1") (pintype "passive"))
      (node (ref "SW17") (pin "A2") (pinfunction "2_A2") (pintype "passive"))
    )
    (net (code "35") (name "Net-(IC1D-I1)") (class "Default")
      (node (ref "C19") (pin "2") (pinfunction "2_2") (pintype "passive"))
      (node (ref "IC1") (pin "13") (pinfunction "I1_13") (pintype "input"))
      (node (ref "POT16") (pin "1") (pinfunction "1_1") (pintype "passive"))
      (node (ref "POT16") (pin "2") (pinfunction "2_2") (pintype "passive"))
    )
    (net (code "36") (name "Net-(IC1D-O)") (class "Default")
      (node (ref "IC1") (pin "11") (pinfunction "O_11") (pintype "output"))
      (node (ref "POT16") (pin "3") (pinfunction "3_3") (pintype "passive"))
      (node (ref "R28") (pin "2") (pinfunction "2_2") (pintype "passive"))
    )
    (net (code "37") (name "Net-(IC3A--IN)") (class "Default")
      (node (ref "IC3") (pin "2") (pinfunction "-IN_2") (pintype "input"))
      (node (ref "R18") (pin "1") (pinfunction "1_1") (pintype "passive"))
      (node (ref "R19") (pin "1") (pinfunction "1_1") (pintype "passive"))
      (node (ref "R20") (pin "1") (pinfunction "1_1") (pintype "passive"))
      (node (ref "R21") (pin "1") (pinfunction "1_1") (pintype "passive"))
      (node (ref "R23") (pin "2") (pinfunction "2_2") (pintype "passive"))
    )
    (net (code "38") (name "Net-(IC3A-OUT)") (class "Default")
      (node (ref "IC3") (pin "1") (pinfunction "OUT_1") (pintype "output"))
      (node (ref "IC3") (pin "6") (pinfunction "-IN_6") (pintype "input"))
      (node (ref "R23") (pin "1") (pinfunction "1_1") (pintype "passive"))
      (node (ref "R24") (pin "2") (pinfunction "2_2") (pintype "passive"))
    )
    (net (code "39") (name "Net-(IC3B-OUT)") (class "Default")
      (node (ref "IC3") (pin "7") (pinfunction "OUT_7") (pintype "output"))
      (node (ref "R24") (pin "1") (pinfunction "1_1") (pintype "passive"))
      (node (ref "R25") (pin "2") (pinfunction "2_2") (pintype "passive"))
    )
    (net (code "40") (name "Net-(POT1-Pad1)") (class "Default")
      (node (ref "POT1") (pin "1") (pinfunction "1_1") (pintype "passive"))
      (node (ref "POT2") (pin "3") (pinfunction "3_3") (pintype "passive"))
    )
    (net (code "41") (name "Net-(POT1-Pad2)") (class "Default")
      (node (ref "POT1") (pin "2") (pinfunction "2_2") (pintype "passive"))
      (node (ref "R12") (pin "1") (pinfunction "1_1") (pintype "passive"))
    )
    (net (code "42") (name "Net-(POT1-Pad3)") (class "Default")
      (node (ref "POT1") (pin "3") (pinfunction "3_3") (pintype "passive"))
      (node (ref "POT11") (pin "3") (pinfunction "3_3") (pintype "passive"))
    )
    (net (code "43") (name "Net-(POT6-Pad3)") (class "Default")
      (node (ref "POT6") (pin "3") (pinfunction "3_3") (pintype "passive"))
      (node (ref "POT7") (pin "3") (pinfunction "3_3") (pintype "passive"))
    )
    (net (code "44") (name "Net-(POT7-Pad1)") (class "Default")
      (node (ref "POT7") (pin "1") (pinfunction "1_1") (pintype "passive"))
      (node (ref "POT8") (pin "3") (pinfunction "3_3") (pintype "passive"))
    )
    (net (code "45") (name "Net-(POT7-Pad2)") (class "Default")
      (node (ref "POT7") (pin "2") (pinfunction "2_2") (pintype "passive"))
      (node (ref "R6") (pin "1") (pinfunction "1_1") (pintype "passive"))
    )
    (net (code "46") (name "Net-(POT12-Pad3)") (class "Default")
      (node (ref "POT12") (pin "3") (pinfunction "3_3") (pintype "passive"))
      (node (ref "POT13") (pin "3") (pinfunction "3_3") (pintype "passive"))
    )
    (net (code "47") (name "Net-(POT13-Pad1)") (class "Default")
      (node (ref "POT13") (pin "1") (pinfunction "1_1") (pintype "passive"))
      (node (ref "POT14") (pin "3") (pinfunction "3_3") (pintype "passive"))
    )
    (net (code "48") (name "Net-(POT13-Pad2)") (class "Default")
      (node (ref "POT13") (pin "2") (pinfunction "2_2") (pintype "passive"))
      (node (ref "R14") (pin "1") (pinfunction "1_1") (pintype "passive"))
    )
    (net (code "49") (name "Net-(POT17-Pad3)") (class "Default")
      (node (ref "POT17") (pin "3") (pinfunction "3_3") (pintype "passive"))
      (node (ref "POT18") (pin "3") (pinfunction "3_3") (pintype "passive"))
    )
    (net (code "50") (name "Net-(POT18-Pad1)") (class "Default")
      (node (ref "POT18") (pin "1") (pinfunction "1_1") (pintype "passive"))
      (node (ref "POT19") (pin "3") (pinfunction "3_3") (pintype "passive"))
    )
    (net (code "51") (name "Net-(POT18-Pad2)") (class "Default")
      (node (ref "POT18") (pin "2") (pinfunction "2_2") (pintype "passive"))
      (node (ref "R28") (pin "1") (pinfunction "1_1") (pintype "passive"))
    )
    (net (code "52") (name "Net-(POT21-Pad2)") (class "Default")
      (node (ref "POT21") (pin "2") (pinfunction "2_2") (pintype "passive"))
      (node (ref "U$11") (pin "TIP") (pinfunction "TIP_TIP") (pintype "passive"))
    )
    (net (code "53") (name "Net-(R1-Pad2)") (class "Default")
      (node (ref "R1") (pin "2") (pinfunction "2_2") (pintype "passive"))
      (node (ref "SW2") (pin "A") (pinfunction "A_A") (pintype "passive"))
    )
    (net (code "54") (name "Net-(R3-Pad2)") (class "Default")
      (node (ref "R3") (pin "2") (pinfunction "2_2") (pintype "passive"))
      (node (ref "SW1") (pin "B") (pinfunction "B_B") (pintype "passive"))
    )
    (net (code "55") (name "Net-(R5-Pad2)") (class "Default")
      (node (ref "R5") (pin "2") (pinfunction "2_2") (pintype "passive"))
      (node (ref "SW1") (pin "A") (pinfunction "A_A") (pintype "passive"))
    )
    (net (code "56") (name "Net-(R8-Pad2)") (class "Default")
      (node (ref "R8") (pin "2") (pinfunction "2_2") (pintype "passive"))
      (node (ref "SW4") (pin "B") (pinfunction "B_B") (pintype "passive"))
    )
    (net (code "57") (name "Net-(R10-Pad2)") (class "Default")
      (node (ref "R10") (pin "2") (pinfunction "2_2") (pintype "passive"))
      (node (ref "SW7") (pin "A") (pinfunction "A_A") (pintype "passive"))
    )
    (net (code "58") (name "Net-(R13-Pad2)") (class "Default")
      (node (ref "R13") (pin "2") (pinfunction "2_2") (pintype "passive"))
      (node (ref "SW4") (pin "A") (pinfunction "A_A") (pintype "passive"))
    )
    (net (code "59") (name "Net-(R16-Pad2)") (class "Default")
      (node (ref "R16") (pin "2") (pinfunction "2_2") (pintype "passive"))
      (node (ref "SW10") (pin "B") (pinfunction "B_B") (pintype "passive"))
    )
    (net (code "60") (name "Net-(R17-Pad2)") (class "Default")
      (node (ref "R17") (pin "2") (pinfunction "2_2") (pintype "passive"))
      (node (ref "SW11") (pin "A") (pinfunction "A_A") (pintype "passive"))
    )
    (net (code "61") (name "Net-(R27-Pad2)") (class "Default")
      (node (ref "R27") (pin "2") (pinfunction "2_2") (pintype "passive"))
      (node (ref "SW10") (pin "A") (pinfunction "A_A") (pintype "passive"))
    )
    (net (code "62") (name "Net-(R30-Pad2)") (class "Default")
      (node (ref "R30") (pin "2") (pinfunction "2_2") (pintype "passive"))
      (node (ref "SW14") (pin "B") (pinfunction "B_B") (pintype "passive"))
    )
    (net (code "63") (name "Net-(R31-Pad2)") (class "Default")
      (node (ref "R31") (pin "2") (pinfunction "2_2") (pintype "passive"))
      (node (ref "SW15") (pin "A") (pinfunction "A_A") (pintype "passive"))
    )
    (net (code "64") (name "Net-(R33-Pad2)") (class "Default")
      (node (ref "R33") (pin "2") (pinfunction "2_2") (pintype "passive"))
      (node (ref "SW14") (pin "A") (pinfunction "A_A") (pintype "passive"))
    )
    (net (code "65") (name "Net-(SW1-COM)") (class "Default")
      (node (ref "SW1") (pin "C") (pinfunction "COM_C") (pintype "passive"))
      (node (ref "SW6") (pin "A3") (pinfunction "3_A3") (pintype "passive"))
    )
    (net (code "66") (name "Net-(SW2-COM)") (class "Default")
      (node (ref "SW2") (pin "C") (pinfunction "COM_C") (pintype "passive"))
      (node (ref "SW6") (pin "B3") (pinfunction "3_B3") (pintype "passive"))
    )
    (net (code "67") (name "Net-(SW3-COM)") (class "Default")
      (node (ref "SW3") (pin "C") (pinfunction "COM_C") (pintype "passive"))
      (node (ref "U1") (pin "5") (pinfunction "CV_5") (pintype "passive"))
    )
    (net (code "68") (name "Net-(SW4-COM)") (class "Default")
      (node (ref "SW4") (pin "C") (pinfunction "COM_C") (pintype "passive"))
      (node (ref "SW9") (pin "A3") (pinfunction "3_A3") (pintype "passive"))
    )
    (net (code "69") (name "Net-(SW6B-2)") (class "Default")
      (node (ref "SW6") (pin "B2") (pinfunction "2_B2") (pintype "passive"))
      (node (ref "U1") (pin "4") (pinfunction "RESET_4") (pintype "input"))
    )
    (net (code "70") (name "Net-(SW7-COM)") (class "Default")
      (node (ref "SW7") (pin "C") (pinfunction "COM_C") (pintype "passive"))
      (node (ref "SW9") (pin "B3") (pinfunction "3_B3") (pintype "passive"))
    )
    (net (code "71") (name "Net-(SW8-COM)") (class "Default")
      (node (ref "SW8") (pin "C") (pinfunction "COM_C") (pintype "passive"))
      (node (ref "U2") (pin "5") (pinfunction "CV_5") (pintype "passive"))
    )
    (net (code "72") (name "Net-(SW9B-2)") (class "Default")
      (node (ref "SW9") (pin "B2") (pinfunction "2_B2") (pintype "passive"))
      (node (ref "U2") (pin "4") (pinfunction "RESET_4") (pintype "input"))
    )
    (net (code "73") (name "Net-(SW10-COM)") (class "Default")
      (node (ref "SW10") (pin "C") (pinfunction "COM_C") (pintype "passive"))
      (node (ref "SW13") (pin "A3") (pinfunction "3_A3") (pintype "passive"))
    )
    (net (code "74") (name "Net-(SW11-COM)") (class "Default")
      (node (ref "SW11") (pin "C") (pinfunction "COM_C") (pintype "passive"))
      (node (ref "SW13") (pin "B3") (pinfunction "3_B3") (pintype "passive"))
    )
    (net (code "75") (name "Net-(SW12-COM)") (class "Default")
      (node (ref "SW12") (pin "C") (pinfunction "COM_C") (pintype "passive"))
      (node (ref "U3") (pin "5") (pinfunction "CV_5") (pintype "passive"))
    )
    (net (code "76") (name "Net-(SW13B-2)") (class "Default")
      (node (ref "SW13") (pin "B2") (pinfunction "2_B2") (pintype "passive"))
      (node (ref "U3") (pin "4") (pinfunction "RESET_4") (pintype "input"))
    )
    (net (code "77") (name "Net-(SW14-COM)") (class "Default")
      (node (ref "SW14") (pin "C") (pinfunction "COM_C") (pintype "passive"))
      (node (ref "SW17") (pin "A3") (pinfunction "3_A3") (pintype "passive"))
    )
    (net (code "78") (name "Net-(SW15-COM)") (class "Default")
      (node (ref "SW15") (pin "C") (pinfunction "COM_C") (pintype "passive"))
      (node (ref "SW17") (pin "B3") (pinfunction "3_B3") (pintype "passive"))
    )
    (net (code "79") (name "Net-(SW16-COM)") (class "Default")
      (node (ref "SW16") (pin "C") (pinfunction "COM_C") (pintype "passive"))
      (node (ref "U4") (pin "5") (pinfunction "CV_5") (pintype "passive"))
    )
    (net (code "80") (name "Net-(SW17B-2)") (class "Default")
      (node (ref "SW17") (pin "B2") (pinfunction "2_B2") (pintype "passive"))
      (node (ref "U4") (pin "4") (pinfunction "RESET_4") (pintype "input"))
    )
    (net (code "81") (name "Net-(SW18-PadA)") (class "Default")
      (node (ref "SW18") (pin "A") (pinfunction "A_A") (pintype "passive"))
      (node (ref "U$10") (pin "SLEEVE") (pinfunction "SLEEVE_SLEEVE") (pintype "bidirectional"))
    )
    (net (code "82") (name "Net-(U$10-PadCONNECT)") (class "Default")
      (node (ref "U$10") (pin "CONNECT") (pinfunction "CONNECT_CONNECT") (pintype "bidirectional"))
      (node (ref "U$9") (pin "9V_BATTERY_+") (pinfunction "9V_BATTERY_+_9V_BATTERY_+") (pintype "power_in"))
    )
    (net (code "83") (name "Net-(U1-DISCH)") (class "Default")
      (node (ref "POT4") (pin "1") (pinfunction "1_1") (pintype "passive"))
      (node (ref "POT4") (pin "2") (pinfunction "2_2") (pintype "passive"))
      (node (ref "R4") (pin "2") (pinfunction "2_2") (pintype "passive"))
      (node (ref "U1") (pin "7") (pinfunction "DISCH_7") (pintype "input"))
    )
    (net (code "84") (name "Net-(U1-OUT)") (class "Default")
      (node (ref "R5") (pin "1") (pinfunction "1_1") (pintype "passive"))
      (node (ref "U1") (pin "3") (pinfunction "OUT_3") (pintype "output"))
    )
    (net (code "85") (name "Net-(U1-TRIG)") (class "Default")
      (node (ref "C3") (pin "+") (pinfunction "+_+") (pintype "passive"))
      (node (ref "U1") (pin "2") (pinfunction "TRIG_2") (pintype "bidirectional"))
    )
    (net (code "86") (name "Net-(U1-TRSH)") (class "Default")
      (node (ref "POT4") (pin "3") (pinfunction "3_3") (pintype "passive"))
      (node (ref "U1") (pin "6") (pinfunction "TRSH_6") (pintype "input"))
    )
    (net (code "87") (name "Net-(U2-DISCH)") (class "Default")
      (node (ref "POT9") (pin "1") (pinfunction "1_1") (pintype "passive"))
      (node (ref "POT9") (pin "2") (pinfunction "2_2") (pintype "passive"))
      (node (ref "R11") (pin "2") (pinfunction "2_2") (pintype "passive"))
      (node (ref "U2") (pin "7") (pinfunction "DISCH_7") (pintype "input"))
    )
    (net (code "88") (name "Net-(U2-OUT)") (class "Default")
      (node (ref "R13") (pin "1") (pinfunction "1_1") (pintype "passive"))
      (node (ref "U2") (pin "3") (pinfunction "OUT_3") (pintype "output"))
    )
    (net (code "89") (name "Net-(U2-TRIG)") (class "Default")
      (node (ref "C7") (pin "+") (pinfunction "+_+") (pintype "passive"))
      (node (ref "U2") (pin "2") (pinfunction "TRIG_2") (pintype "bidirectional"))
    )
    (net (code "90") (name "Net-(U2-TRSH)") (class "Default")
      (node (ref "POT9") (pin "3") (pinfunction "3_3") (pintype "passive"))
      (node (ref "U2") (pin "6") (pinfunction "TRSH_6") (pintype "input"))
    )
    (net (code "91") (name "Net-(U3-DISCH)") (class "Default")
      (node (ref "POT15") (pin "1") (pinfunction "1_1") (pintype "passive"))
      (node (ref "POT15") (pin "2") (pinfunction "2_2") (pintype "passive"))
      (node (ref "R26") (pin "2") (pinfunction "2_2") (pintype "passive"))
      (node (ref "U3") (pin "7") (pinfunction "DISCH_7") (pintype "input"))
    )
    (net (code "92") (name "Net-(U3-OUT)") (class "Default")
      (node (ref "R27") (pin "1") (pinfunction "1_1") (pintype "passive"))
      (node (ref "U3") (pin "3") (pinfunction "OUT_3") (pintype "output"))
    )
    (net (code "93") (name "Net-(U3-TRIG)") (class "Default")
      (node (ref "C15") (pin "+") (pinfunction "+_+") (pintype "passive"))
      (node (ref "U3") (pin "2") (pinfunction "TRIG_2") (pintype "bidirectional"))
    )
    (net (code "94") (name "Net-(U3-TRSH)") (class "Default")
      (node (ref "POT15") (pin "3") (pinfunction "3_3") (pintype "passive"))
      (node (ref "U3") (pin "6") (pinfunction "TRSH_6") (pintype "input"))
    )
    (net (code "95") (name "Net-(U4-DISCH)") (class "Default")
      (node (ref "POT20") (pin "1") (pinfunction "1_1") (pintype "passive"))
      (node (ref "POT20") (pin "2") (pinfunction "2_2") (pintype "passive"))
      (node (ref "R32") (pin "2") (pinfunction "2_2") (pintype "passive"))
      (node (ref "U4") (pin "7") (pinfunction "DISCH_7") (pintype "input"))
    )
    (net (code "96") (name "Net-(U4-OUT)") (class "Default")
      (node (ref "R33") (pin "1") (pinfunction "1_1") (pintype "passive"))
      (node (ref "U4") (pin "3") (pinfunction "OUT_3") (pintype "output"))
    )
    (net (code "97") (name "Net-(U4-TRIG)") (class "Default")
      (node (ref "C21") (pin "+") (pinfunction "+_+") (pintype "passive"))
      (node (ref "U4") (pin "2") (pinfunction "TRIG_2") (pintype "bidirectional"))
    )
    (net (code "98") (name "Net-(U4-TRSH)") (class "Default")
      (node (ref "POT20") (pin "3") (pinfunction "3_3") (pintype "passive"))
      (node (ref "U4") (pin "6") (pinfunction "TRSH_6") (pintype "input"))
    )
    (net (code "99") (name "VCC") (class "Default")
      (node (ref "C10") (pin "2") (pinfunction "2_2") (pintype "passive"))
      (node (ref "C11") (pin "2") (pinfunction "2_2") (pintype "passive"))
      (node (ref "C12") (pin "2") (pinfunction "2_2") (pintype "passive"))
      (node (ref "C13") (pin "2") (pinfunction "2_2") (pintype "passive"))
      (node (ref "C18") (pin "2") (pinfunction "2_2") (pintype "passive"))
      (node (ref "C2") (pin "2") (pinfunction "2_2") (pintype "passive"))
      (node (ref "C23") (pin "2") (pinfunction "2_2") (pintype "passive"))
      (node (ref "C25") (pin "+") (pinfunction "+_+") (pintype "passive"))
      (node (ref "D5") (pin "A") (pinfunction "A_A") (pintype "passive"))
      (node (ref "IC1") (pin "14") (pinfunction "VDD_14") (pintype "power_in"))
      (node (ref "IC3") (pin "8") (pinfunction "V+_8") (pintype "power_in"))
      (node (ref "R1") (pin "1") (pinfunction "1_1") (pintype "passive"))
      (node (ref "R10") (pin "1") (pinfunction "1_1") (pintype "passive"))
      (node (ref "R11") (pin "1") (pinfunction "1_1") (pintype "passive"))
      (node (ref "R16") (pin "1") (pinfunction "1_1") (pintype "passive"))
      (node (ref "R17") (pin "1") (pinfunction "1_1") (pintype "passive"))
      (node (ref "R26") (pin "1") (pinfunction "1_1") (pintype "passive"))
      (node (ref "R3") (pin "1") (pinfunction "1_1") (pintype "passive"))
      (node (ref "R30") (pin "1") (pinfunction "1_1") (pintype "passive"))
      (node (ref "R31") (pin "1") (pinfunction "1_1") (pintype "passive"))
      (node (ref "R32") (pin "1") (pinfunction "1_1") (pintype "passive"))
      (node (ref "R4") (pin "1") (pinfunction "1_1") (pintype "passive"))
      (node (ref "R8") (pin "1") (pinfunction "1_1") (pintype "passive"))
      (node (ref "SW18") (pin "B") (pinfunction "B_B") (pintype "passive"))
      (node (ref "U1") (pin "8") (pinfunction "V+_8") (pintype "power_in"))
      (node (ref "U2") (pin "8") (pinfunction "V+_8") (pintype "power_in"))
      (node (ref "U3") (pin "8") (pinfunction "V+_8") (pintype "power_in"))
      (node (ref "U4") (pin "8") (pinfunction "V+_8") (pintype "power_in"))
    )
  )
)
